# Pixel8x4U.net
KiCad netlist of a schematic drawn in EAGLE
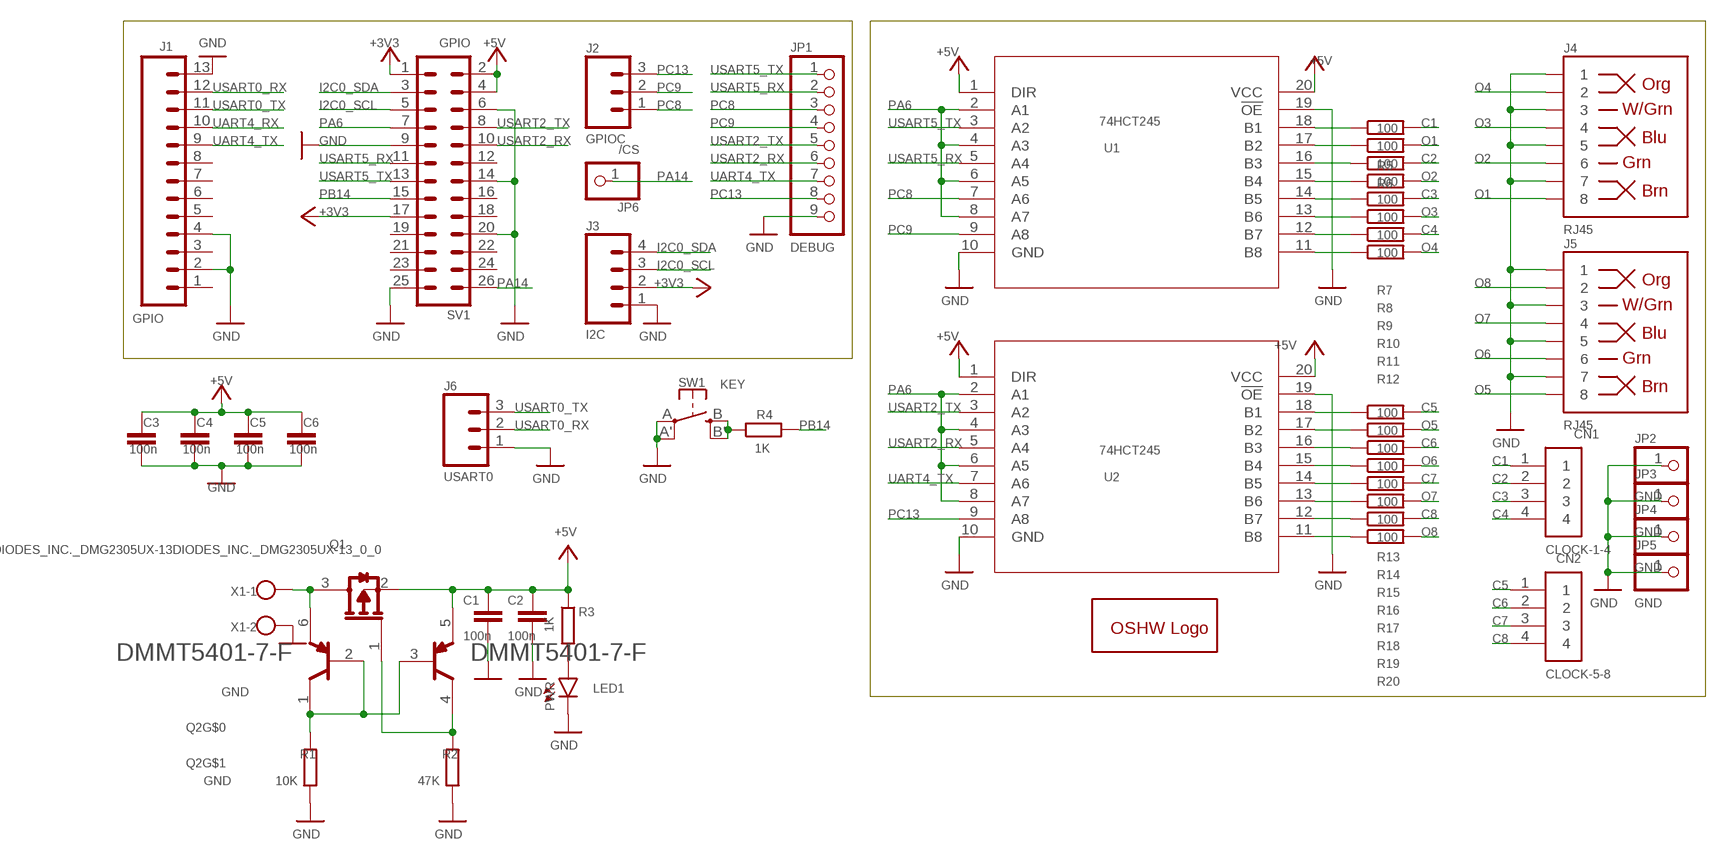
[diagram p0: schematic, sheet 1]

(export (version "E")
  (design (tool "Eeschema 10.0.6"))
  (components
    (comp (ref "C1")
      (value "100n")
      (footprint "eagle-import:C0603")
      (libsource (lib "eagle-import") (part "C-EUC0603"))
    )
    (comp (ref "C2")
      (value "100n")
      (footprint "eagle-import:C0603")
      (libsource (lib "eagle-import") (part "C-EUC0603"))
    )
    (comp (ref "C3")
      (value "100n")
      (footprint "eagle-import:C0603")
      (libsource (lib "eagle-import") (part "C-EUC0603"))
    )
    (comp (ref "C4")
      (value "100n")
      (footprint "eagle-import:C0603")
      (libsource (lib "eagle-import") (part "C-EUC0603"))
    )
    (comp (ref "C5")
      (value "100n")
      (footprint "eagle-import:C0603")
      (libsource (lib "eagle-import") (part "C-EUC0603"))
    )
    (comp (ref "C6")
      (value "100n")
      (footprint "eagle-import:C0603")
      (libsource (lib "eagle-import") (part "C-EUC0603"))
    )
    (comp (ref "CN1")
      (value "CLOCK-1-4")
      (footprint "eagle-import:1X04-CLEANBIG")
      (libsource (lib "eagle-import") (part "1X4-CLEANBIG"))
    )
    (comp (ref "CN2")
      (value "CLOCK-5-8")
      (footprint "eagle-import:1X04-CLEANBIG")
      (libsource (lib "eagle-import") (part "1X4-CLEANBIG"))
    )
    (comp (ref "GOLD_ORB_SM1")
      (value "OSHWLOGOLOGO5MM")
      (footprint "eagle-import:OSHW_5MM")
      (libsource (lib "eagle-import") (part "OSHWLOGOLOGO5MM"))
    )
    (comp (ref "J1")
      (value "GPIO")
      (footprint "eagle-import:1X13")
      (libsource (lib "eagle-import") (part "CONN_13"))
    )
    (comp (ref "J2")
      (value "GPIOC")
      (footprint "eagle-import:1X03")
      (libsource (lib "eagle-import") (part "CONN_03"))
    )
    (comp (ref "J3")
      (value "I2C")
      (footprint "eagle-import:1X04")
      (libsource (lib "eagle-import") (part "CONN_04"))
    )
    (comp (ref "J4")
      (value "RJ45")
      (footprint "eagle-import:RJ45-8")
      (libsource (lib "eagle-import") (part "RJ45-8"))
    )
    (comp (ref "J5")
      (value "RJ45")
      (footprint "eagle-import:RJ45-8")
      (libsource (lib "eagle-import") (part "RJ45-8"))
    )
    (comp (ref "J6")
      (value "USART0")
      (footprint "eagle-import:1X03")
      (libsource (lib "eagle-import") (part "CONN_03"))
    )
    (comp (ref "JP1")
      (value "DEBUG")
      (footprint "eagle-import:1X09")
      (libsource (lib "eagle-import") (part "PINHD-1X9"))
    )
    (comp (ref "JP2")
      (value "GND")
      (footprint "eagle-import:1X01-CLEANBIG")
      (libsource (lib "eagle-import") (part "PINHD-1X1CB"))
    )
    (comp (ref "JP3")
      (value "GND")
      (footprint "eagle-import:1X01-CLEANBIG")
      (libsource (lib "eagle-import") (part "PINHD-1X1CB"))
    )
    (comp (ref "JP4")
      (value "GND")
      (footprint "eagle-import:1X01-CLEANBIG")
      (libsource (lib "eagle-import") (part "PINHD-1X1CB"))
    )
    (comp (ref "JP5")
      (value "GND")
      (footprint "eagle-import:1X01-CLEANBIG")
      (libsource (lib "eagle-import") (part "PINHD-1X1CB"))
    )
    (comp (ref "JP6")
      (value "/CS")
      (footprint "eagle-import:1X01-CLEANBIG")
      (libsource (lib "eagle-import") (part "PINHD-1X1CB"))
    )
    (comp (ref "LED1")
      (value "PWR")
      (footprint "eagle-import:CHIP-LED0603")
      (libsource (lib "eagle-import") (part "LEDCHIP-LED0603"))
    )
    (comp (ref "Q1")
      (value "DIODES_INC._DMG2305UX-13DIODES_INC._DMG2305UX-13_0_0")
      (footprint "eagle-import:DIODES_INC._DMG2305UX-13_0")
      (fields
        (field (name "DIGIKEY_PART_NUMBER") "DMG2305UX-13DICT-ND")
        (field (name "MF") "Diodes Inc.")
        (field (name "MOUSER_PART_NUMBER") "621-DMG2305UX-13")
      )
      (libsource (lib "eagle-import") (part "DIODES_INC._DMG2305UX-13DIODES_INC._DMG2305UX-13_0_0"))
    )
    (comp (ref "Q2")
      (value "DMMT5401-7-F_0_0")
      (footprint "eagle-import:DIODES_DMMT5401-7-F_0")
      (fields
        (field (name "DIGIKEY_PART_NUMBER") "DMMT5401-FDICT-ND")
        (field (name "MF") "Diodes")
        (field (name "MOUSER_PART_NUMBER") "621-DMMT5401-7-F")
      )
      (libsource (lib "eagle-import") (part "DIODES_DMMT5401-7-FDIODES_DMMT5401-7-F_0_0"))
    )
    (comp (ref "R1")
      (value "10K")
      (footprint "eagle-import:R0402")
      (libsource (lib "eagle-import") (part "R-EU_R0402"))
    )
    (comp (ref "R2")
      (value "47K")
      (footprint "eagle-import:R0402")
      (libsource (lib "eagle-import") (part "R-EU_R0402"))
    )
    (comp (ref "R3")
      (value "1K")
      (footprint "eagle-import:R0402")
      (libsource (lib "eagle-import") (part "resistor_348_R-EU_R0402"))
    )
    (comp (ref "R4")
      (value "1K")
      (footprint "eagle-import:R0402")
      (libsource (lib "eagle-import") (part "resistor_348_R-EU_R0402"))
    )
    (comp (ref "R5")
      (value "100")
      (footprint "eagle-import:R0402")
      (libsource (lib "eagle-import") (part "R-EU_R0402"))
    )
    (comp (ref "R6")
      (value "100")
      (footprint "eagle-import:R0402")
      (libsource (lib "eagle-import") (part "R-EU_R0402"))
    )
    (comp (ref "R7")
      (value "100")
      (footprint "eagle-import:R0402")
      (libsource (lib "eagle-import") (part "R-EU_R0402"))
    )
    (comp (ref "R8")
      (value "100")
      (footprint "eagle-import:R0402")
      (libsource (lib "eagle-import") (part "R-EU_R0402"))
    )
    (comp (ref "R9")
      (value "100")
      (footprint "eagle-import:R0402")
      (libsource (lib "eagle-import") (part "R-EU_R0402"))
    )
    (comp (ref "R10")
      (value "100")
      (footprint "eagle-import:R0402")
      (libsource (lib "eagle-import") (part "R-EU_R0402"))
    )
    (comp (ref "R11")
      (value "100")
      (footprint "eagle-import:R0402")
      (libsource (lib "eagle-import") (part "R-EU_R0402"))
    )
    (comp (ref "R12")
      (value "100")
      (footprint "eagle-import:R0402")
      (libsource (lib "eagle-import") (part "R-EU_R0402"))
    )
    (comp (ref "R13")
      (value "100")
      (footprint "eagle-import:R0402")
      (libsource (lib "eagle-import") (part "R-EU_R0402"))
    )
    (comp (ref "R14")
      (value "100")
      (footprint "eagle-import:R0402")
      (libsource (lib "eagle-import") (part "R-EU_R0402"))
    )
    (comp (ref "R15")
      (value "100")
      (footprint "eagle-import:R0402")
      (libsource (lib "eagle-import") (part "R-EU_R0402"))
    )
    (comp (ref "R16")
      (value "100")
      (footprint "eagle-import:R0402")
      (libsource (lib "eagle-import") (part "R-EU_R0402"))
    )
    (comp (ref "R17")
      (value "100")
      (footprint "eagle-import:R0402")
      (libsource (lib "eagle-import") (part "R-EU_R0402"))
    )
    (comp (ref "R18")
      (value "100")
      (footprint "eagle-import:R0402")
      (libsource (lib "eagle-import") (part "R-EU_R0402"))
    )
    (comp (ref "R19")
      (value "100")
      (footprint "eagle-import:R0402")
      (libsource (lib "eagle-import") (part "R-EU_R0402"))
    )
    (comp (ref "R20")
      (value "100")
      (footprint "eagle-import:R0402")
      (libsource (lib "eagle-import") (part "R-EU_R0402"))
    )
    (comp (ref "SV1")
      (value "GPIO")
      (footprint "eagle-import:MA13-2")
      (libsource (lib "eagle-import") (part "MA13-2"))
    )
    (comp (ref "SW1")
      (value "KEY")
      (footprint "eagle-import:EVQ-Q2")
      (libsource (lib "eagle-import") (part "SPST_TACT-EVQQ2"))
    )
    (comp (ref "U1")
      (value "74HCT245")
      (footprint "eagle-import:PW20")
      (fields
        (field (name "GENERIC_PART_NUMBER") "SN74HCT245")
        (field (name "MANUFACTURER") "Texas Instruments")
        (field (name "MANUFACTURER_PART_NUMBER") "SN74HCT245PWR")
      )
      (libsource (lib "eagle-import") (part "SN74HCT245PWR"))
    )
    (comp (ref "U2")
      (value "74HCT245")
      (footprint "eagle-import:PW20")
      (fields
        (field (name "GENERIC_PART_NUMBER") "SN74HCT245")
        (field (name "MANUFACTURER") "Texas Instruments")
        (field (name "MANUFACTURER_PART_NUMBER") "SN74HCT245PWR")
      )
      (libsource (lib "eagle-import") (part "SN74HCT245PWR"))
    )
    (comp (ref "X1")
      (value "W237-102")
      (footprint "eagle-import:W237-102")
      (fields (field (name "MPN") "237-102"))
      (libsource (lib "eagle-import") (part "W237-102"))
    )
  )
  (nets
    (net (code "1") (name "+3V3") (class "Default")
      (node (ref "J3") (pin "2") (pinfunction "2_2") (pintype "passive"))
      (node (ref "SV1") (pin "1") (pinfunction "1_1") (pintype "passive"))
      (node (ref "SV1") (pin "17") (pinfunction "17_17") (pintype "passive"))
    )
    (net (code "2") (name "+5V") (class "Default")
      (node (ref "C1") (pin "1") (pinfunction "1_1") (pintype "passive"))
      (node (ref "C2") (pin "1") (pinfunction "1_1") (pintype "passive"))
      (node (ref "C3") (pin "1") (pinfunction "1_1") (pintype "passive"))
      (node (ref "C4") (pin "1") (pinfunction "1_1") (pintype "passive"))
      (node (ref "C5") (pin "1") (pinfunction "1_1") (pintype "passive"))
      (node (ref "C6") (pin "1") (pinfunction "1_1") (pintype "passive"))
      (node (ref "Q1") (pin "2") (pinfunction "S_2") (pintype "passive"))
      (node (ref "Q2") (pin "5") (pinfunction "E2_5") (pintype "passive"))
      (node (ref "R3") (pin "1") (pinfunction "1_1") (pintype "passive"))
      (node (ref "SV1") (pin "2") (pinfunction "2_2") (pintype "passive"))
      (node (ref "SV1") (pin "4") (pinfunction "4_4") (pintype "passive"))
      (node (ref "U1") (pin "1") (pinfunction "DIR_1") (pintype "input"))
      (node (ref "U1") (pin "20") (pinfunction "VCC_20") (pintype "power_in"))
      (node (ref "U2") (pin "1") (pinfunction "DIR_1") (pintype "input"))
      (node (ref "U2") (pin "20") (pinfunction "VCC_20") (pintype "power_in"))
    )
    (net (code "3") (name "/C1") (class "Default")
      (node (ref "CN1") (pin "1") (pinfunction "1_1") (pintype "bidirectional"))
      (node (ref "R5") (pin "2") (pinfunction "2_2") (pintype "passive"))
    )
    (net (code "4") (name "/C2") (class "Default")
      (node (ref "CN1") (pin "2") (pinfunction "2_2") (pintype "bidirectional"))
      (node (ref "R7") (pin "2") (pinfunction "2_2") (pintype "passive"))
    )
    (net (code "5") (name "/C3") (class "Default")
      (node (ref "CN1") (pin "3") (pinfunction "3_3") (pintype "bidirectional"))
      (node (ref "R9") (pin "2") (pinfunction "2_2") (pintype "passive"))
    )
    (net (code "6") (name "/C4") (class "Default")
      (node (ref "CN1") (pin "4") (pinfunction "4_4") (pintype "bidirectional"))
      (node (ref "R11") (pin "2") (pinfunction "2_2") (pintype "passive"))
    )
    (net (code "7") (name "/C5") (class "Default")
      (node (ref "CN2") (pin "1") (pinfunction "1_1") (pintype "bidirectional"))
      (node (ref "R13") (pin "2") (pinfunction "2_2") (pintype "passive"))
    )
    (net (code "8") (name "/C6") (class "Default")
      (node (ref "CN2") (pin "2") (pinfunction "2_2") (pintype "bidirectional"))
      (node (ref "R15") (pin "2") (pinfunction "2_2") (pintype "passive"))
    )
    (net (code "9") (name "/C7") (class "Default")
      (node (ref "CN2") (pin "3") (pinfunction "3_3") (pintype "bidirectional"))
      (node (ref "R17") (pin "2") (pinfunction "2_2") (pintype "passive"))
    )
    (net (code "10") (name "/C8") (class "Default")
      (node (ref "CN2") (pin "4") (pinfunction "4_4") (pintype "bidirectional"))
      (node (ref "R19") (pin "2") (pinfunction "2_2") (pintype "passive"))
    )
    (net (code "11") (name "/I2C0_SCL") (class "Default")
      (node (ref "J3") (pin "3") (pinfunction "3_3") (pintype "passive"))
      (node (ref "SV1") (pin "5") (pinfunction "5_5") (pintype "passive"))
    )
    (net (code "12") (name "/I2C0_SDA") (class "Default")
      (node (ref "J3") (pin "4") (pinfunction "4_4") (pintype "passive"))
      (node (ref "SV1") (pin "3") (pinfunction "3_3") (pintype "passive"))
    )
    (net (code "13") (name "/O1") (class "Default")
      (node (ref "J4") (pin "8") (pinfunction "8_8") (pintype "bidirectional"))
      (node (ref "R6") (pin "2") (pinfunction "2_2") (pintype "passive"))
    )
    (net (code "14") (name "/O2") (class "Default")
      (node (ref "J4") (pin "6") (pinfunction "6_6") (pintype "bidirectional"))
      (node (ref "R8") (pin "2") (pinfunction "2_2") (pintype "passive"))
    )
    (net (code "15") (name "/O3") (class "Default")
      (node (ref "J4") (pin "4") (pinfunction "4_4") (pintype "bidirectional"))
      (node (ref "R10") (pin "2") (pinfunction "2_2") (pintype "passive"))
    )
    (net (code "16") (name "/O4") (class "Default")
      (node (ref "J4") (pin "2") (pinfunction "2_2") (pintype "bidirectional"))
      (node (ref "R12") (pin "2") (pinfunction "2_2") (pintype "passive"))
    )
    (net (code "17") (name "/O5") (class "Default")
      (node (ref "J5") (pin "8") (pinfunction "8_8") (pintype "bidirectional"))
      (node (ref "R14") (pin "2") (pinfunction "2_2") (pintype "passive"))
    )
    (net (code "18") (name "/O6") (class "Default")
      (node (ref "J5") (pin "6") (pinfunction "6_6") (pintype "bidirectional"))
      (node (ref "R16") (pin "2") (pinfunction "2_2") (pintype "passive"))
    )
    (net (code "19") (name "/O7") (class "Default")
      (node (ref "J5") (pin "4") (pinfunction "4_4") (pintype "bidirectional"))
      (node (ref "R18") (pin "2") (pinfunction "2_2") (pintype "passive"))
    )
    (net (code "20") (name "/O8") (class "Default")
      (node (ref "J5") (pin "2") (pinfunction "2_2") (pintype "bidirectional"))
      (node (ref "R20") (pin "2") (pinfunction "2_2") (pintype "passive"))
    )
    (net (code "21") (name "/PA6") (class "Default")
      (node (ref "SV1") (pin "7") (pinfunction "7_7") (pintype "passive"))
      (node (ref "U1") (pin "2") (pinfunction "A1_2") (pintype "bidirectional"))
      (node (ref "U1") (pin "4") (pinfunction "A3_4") (pintype "bidirectional"))
      (node (ref "U1") (pin "6") (pinfunction "A5_6") (pintype "bidirectional"))
      (node (ref "U1") (pin "8") (pinfunction "A7_8") (pintype "bidirectional"))
      (node (ref "U2") (pin "2") (pinfunction "A1_2") (pintype "bidirectional"))
      (node (ref "U2") (pin "4") (pinfunction "A3_4") (pintype "bidirectional"))
      (node (ref "U2") (pin "6") (pinfunction "A5_6") (pintype "bidirectional"))
      (node (ref "U2") (pin "8") (pinfunction "A7_8") (pintype "bidirectional"))
    )
    (net (code "22") (name "/PA14") (class "Default")
      (node (ref "JP6") (pin "1") (pinfunction "1_1") (pintype "passive"))
      (node (ref "SV1") (pin "26") (pinfunction "26_26") (pintype "passive"))
    )
    (net (code "23") (name "/PB14") (class "Default")
      (node (ref "R4") (pin "2") (pinfunction "2_2") (pintype "passive"))
      (node (ref "SV1") (pin "15") (pinfunction "15_15") (pintype "passive"))
    )
    (net (code "24") (name "/PC8") (class "Default")
      (node (ref "J2") (pin "1") (pinfunction "1_1") (pintype "passive"))
      (node (ref "JP1") (pin "3") (pinfunction "3_3") (pintype "passive"))
      (node (ref "U1") (pin "7") (pinfunction "A6_7") (pintype "bidirectional"))
    )
    (net (code "25") (name "/PC9") (class "Default")
      (node (ref "J2") (pin "2") (pinfunction "2_2") (pintype "passive"))
      (node (ref "JP1") (pin "4") (pinfunction "4_4") (pintype "passive"))
      (node (ref "U1") (pin "9") (pinfunction "A8_9") (pintype "bidirectional"))
    )
    (net (code "26") (name "/PC13") (class "Default")
      (node (ref "J2") (pin "3") (pinfunction "3_3") (pintype "passive"))
      (node (ref "JP1") (pin "8") (pinfunction "8_8") (pintype "passive"))
      (node (ref "U2") (pin "9") (pinfunction "A8_9") (pintype "bidirectional"))
    )
    (net (code "27") (name "/UART4_RX") (class "Default")
      (node (ref "J1") (pin "10") (pinfunction "10_10") (pintype "passive"))
    )
    (net (code "28") (name "/UART4_TX") (class "Default")
      (node (ref "J1") (pin "9") (pinfunction "9_9") (pintype "passive"))
      (node (ref "JP1") (pin "7") (pinfunction "7_7") (pintype "passive"))
      (node (ref "U2") (pin "7") (pinfunction "A6_7") (pintype "bidirectional"))
    )
    (net (code "29") (name "/USART0_RX") (class "Default")
      (node (ref "J1") (pin "12") (pinfunction "12_12") (pintype "passive"))
      (node (ref "J6") (pin "2") (pinfunction "2_2") (pintype "passive"))
    )
    (net (code "30") (name "/USART0_TX") (class "Default")
      (node (ref "J1") (pin "11") (pinfunction "11_11") (pintype "passive"))
      (node (ref "J6") (pin "3") (pinfunction "3_3") (pintype "passive"))
    )
    (net (code "31") (name "/USART2_RX") (class "Default")
      (node (ref "JP1") (pin "6") (pinfunction "6_6") (pintype "passive"))
      (node (ref "SV1") (pin "10") (pinfunction "10_10") (pintype "passive"))
      (node (ref "U2") (pin "5") (pinfunction "A4_5") (pintype "bidirectional"))
    )
    (net (code "32") (name "/USART2_TX") (class "Default")
      (node (ref "JP1") (pin "5") (pinfunction "5_5") (pintype "passive"))
      (node (ref "SV1") (pin "8") (pinfunction "8_8") (pintype "passive"))
      (node (ref "U2") (pin "3") (pinfunction "A2_3") (pintype "bidirectional"))
    )
    (net (code "33") (name "/USART5_RX") (class "Default")
      (node (ref "JP1") (pin "2") (pinfunction "2_2") (pintype "passive"))
      (node (ref "SV1") (pin "11") (pinfunction "11_11") (pintype "passive"))
      (node (ref "U1") (pin "5") (pinfunction "A4_5") (pintype "bidirectional"))
    )
    (net (code "34") (name "/USART5_TX") (class "Default")
      (node (ref "JP1") (pin "1") (pinfunction "1_1") (pintype "passive"))
      (node (ref "SV1") (pin "13") (pinfunction "13_13") (pintype "passive"))
      (node (ref "U1") (pin "3") (pinfunction "A2_3") (pintype "bidirectional"))
    )
    (net (code "35") (name "GND") (class "Default")
      (node (ref "C1") (pin "2") (pinfunction "2_2") (pintype "passive"))
      (node (ref "C2") (pin "2") (pinfunction "2_2") (pintype "passive"))
      (node (ref "C3") (pin "2") (pinfunction "2_2") (pintype "passive"))
      (node (ref "C4") (pin "2") (pinfunction "2_2") (pintype "passive"))
      (node (ref "C5") (pin "2") (pinfunction "2_2") (pintype "passive"))
      (node (ref "C6") (pin "2") (pinfunction "2_2") (pintype "passive"))
      (node (ref "J1") (pin "13") (pinfunction "13_13") (pintype "passive"))
      (node (ref "J1") (pin "2") (pinfunction "2_2") (pintype "passive"))
      (node (ref "J1") (pin "4") (pinfunction "4_4") (pintype "passive"))
      (node (ref "J3") (pin "1") (pinfunction "1_1") (pintype "passive"))
      (node (ref "J4") (pin "1") (pinfunction "1_1") (pintype "bidirectional"))
      (node (ref "J4") (pin "3") (pinfunction "3_3") (pintype "bidirectional"))
      (node (ref "J4") (pin "5") (pinfunction "5_5") (pintype "bidirectional"))
      (node (ref "J4") (pin "7") (pinfunction "7_7") (pintype "bidirectional"))
      (node (ref "J5") (pin "1") (pinfunction "1_1") (pintype "bidirectional"))
      (node (ref "J5") (pin "3") (pinfunction "3_3") (pintype "bidirectional"))
      (node (ref "J5") (pin "5") (pinfunction "5_5") (pintype "bidirectional"))
      (node (ref "J5") (pin "7") (pinfunction "7_7") (pintype "bidirectional"))
      (node (ref "J6") (pin "1") (pinfunction "1_1") (pintype "passive"))
      (node (ref "JP1") (pin "9") (pinfunction "9_9") (pintype "passive"))
      (node (ref "JP2") (pin "1") (pinfunction "1_1") (pintype "passive"))
      (node (ref "JP3") (pin "1") (pinfunction "1_1") (pintype "passive"))
      (node (ref "JP4") (pin "1") (pinfunction "1_1") (pintype "passive"))
      (node (ref "JP5") (pin "1") (pinfunction "1_1") (pintype "passive"))
      (node (ref "LED1") (pin "C") (pinfunction "C_C") (pintype "passive"))
      (node (ref "R1") (pin "1") (pinfunction "1_1") (pintype "passive"))
      (node (ref "R2") (pin "1") (pinfunction "1_1") (pintype "passive"))
      (node (ref "SV1") (pin "14") (pinfunction "14_14") (pintype "passive"))
      (node (ref "SV1") (pin "20") (pinfunction "20_20") (pintype "passive"))
      (node (ref "SV1") (pin "25") (pinfunction "25_25") (pintype "passive"))
      (node (ref "SV1") (pin "6") (pinfunction "6_6") (pintype "passive"))
      (node (ref "SV1") (pin "9") (pinfunction "9_9") (pintype "passive"))
      (node (ref "SW1") (pin "A") (pinfunction "P_A") (pintype "passive"))
      (node (ref "SW1") (pin "A'") (pinfunction "P1_A'") (pintype "passive"))
      (node (ref "U1") (pin "10") (pinfunction "GND_10") (pintype "power_in"))
      (node (ref "U1") (pin "19") (pinfunction "~{OE}_19") (pintype "input"))
      (node (ref "U2") (pin "10") (pinfunction "GND_10") (pintype "power_in"))
      (node (ref "U2") (pin "19") (pinfunction "~{OE}_19") (pintype "input"))
      (node (ref "X1") (pin "2") (pinfunction "KL_2") (pintype "passive"))
    )
    (net (code "36") (name "Net-(LED1-PadA)") (class "Default")
      (node (ref "LED1") (pin "A") (pinfunction "A_A") (pintype "passive"))
      (node (ref "R3") (pin "2") (pinfunction "2_2") (pintype "passive"))
    )
    (net (code "37") (name "Net-(Q1-D)") (class "Default")
      (node (ref "Q1") (pin "3") (pinfunction "D_3") (pintype "passive"))
      (node (ref "Q2") (pin "6") (pinfunction "E1_6") (pintype "passive"))
      (node (ref "X1") (pin "1") (pinfunction "KL_1") (pintype "passive"))
    )
    (net (code "38") (name "Net-(Q1-G)") (class "Default")
      (node (ref "Q1") (pin "1") (pinfunction "G_1") (pintype "passive"))
      (node (ref "Q2") (pin "4") (pinfunction "C2_4") (pintype "passive"))
      (node (ref "R2") (pin "2") (pinfunction "2_2") (pintype "passive"))
    )
    (net (code "39") (name "Net-(Q2A-B1)") (class "Default")
      (node (ref "Q2") (pin "1") (pinfunction "C1_1") (pintype "passive"))
      (node (ref "Q2") (pin "2") (pinfunction "B1_2") (pintype "passive"))
      (node (ref "Q2") (pin "3") (pinfunction "B2_3") (pintype "passive"))
      (node (ref "R1") (pin "2") (pinfunction "2_2") (pintype "passive"))
    )
    (net (code "40") (name "Net-(SW1-S)") (class "Default")
      (node (ref "R4") (pin "1") (pinfunction "1_1") (pintype "passive"))
      (node (ref "SW1") (pin "B") (pinfunction "S_B") (pintype "passive"))
      (node (ref "SW1") (pin "B'") (pinfunction "S1_B'") (pintype "passive"))
    )
    (net (code "41") (name "Net-(U1-B1)") (class "Default")
      (node (ref "R5") (pin "1") (pinfunction "1_1") (pintype "passive"))
      (node (ref "U1") (pin "18") (pinfunction "B1_18") (pintype "bidirectional"))
    )
    (net (code "42") (name "Net-(U1-B2)") (class "Default")
      (node (ref "R6") (pin "1") (pinfunction "1_1") (pintype "passive"))
      (node (ref "U1") (pin "17") (pinfunction "B2_17") (pintype "bidirectional"))
    )
    (net (code "43") (name "Net-(U1-B3)") (class "Default")
      (node (ref "R7") (pin "1") (pinfunction "1_1") (pintype "passive"))
      (node (ref "U1") (pin "16") (pinfunction "B3_16") (pintype "bidirectional"))
    )
    (net (code "44") (name "Net-(U1-B4)") (class "Default")
      (node (ref "R8") (pin "1") (pinfunction "1_1") (pintype "passive"))
      (node (ref "U1") (pin "15") (pinfunction "B4_15") (pintype "bidirectional"))
    )
    (net (code "45") (name "Net-(U1-B5)") (class "Default")
      (node (ref "R9") (pin "1") (pinfunction "1_1") (pintype "passive"))
      (node (ref "U1") (pin "14") (pinfunction "B5_14") (pintype "bidirectional"))
    )
    (net (code "46") (name "Net-(U1-B6)") (class "Default")
      (node (ref "R10") (pin "1") (pinfunction "1_1") (pintype "passive"))
      (node (ref "U1") (pin "13") (pinfunction "B6_13") (pintype "bidirectional"))
    )
    (net (code "47") (name "Net-(U1-B7)") (class "Default")
      (node (ref "R11") (pin "1") (pinfunction "1_1") (pintype "passive"))
      (node (ref "U1") (pin "12") (pinfunction "B7_12") (pintype "bidirectional"))
    )
    (net (code "48") (name "Net-(U1-B8)") (class "Default")
      (node (ref "R12") (pin "1") (pinfunction "1_1") (pintype "passive"))
      (node (ref "U1") (pin "11") (pinfunction "B8_11") (pintype "bidirectional"))
    )
    (net (code "49") (name "Net-(U2-B1)") (class "Default")
      (node (ref "R13") (pin "1") (pinfunction "1_1") (pintype "passive"))
      (node (ref "U2") (pin "18") (pinfunction "B1_18") (pintype "bidirectional"))
    )
    (net (code "50") (name "Net-(U2-B2)") (class "Default")
      (node (ref "R14") (pin "1") (pinfunction "1_1") (pintype "passive"))
      (node (ref "U2") (pin "17") (pinfunction "B2_17") (pintype "bidirectional"))
    )
    (net (code "51") (name "Net-(U2-B3)") (class "Default")
      (node (ref "R15") (pin "1") (pinfunction "1_1") (pintype "passive"))
      (node (ref "U2") (pin "16") (pinfunction "B3_16") (pintype "bidirectional"))
    )
    (net (code "52") (name "Net-(U2-B4)") (class "Default")
      (node (ref "R16") (pin "1") (pinfunction "1_1") (pintype "passive"))
      (node (ref "U2") (pin "15") (pinfunction "B4_15") (pintype "bidirectional"))
    )
    (net (code "53") (name "Net-(U2-B5)") (class "Default")
      (node (ref "R17") (pin "1") (pinfunction "1_1") (pintype "passive"))
      (node (ref "U2") (pin "14") (pinfunction "B5_14") (pintype "bidirectional"))
    )
    (net (code "54") (name "Net-(U2-B6)") (class "Default")
      (node (ref "R18") (pin "1") (pinfunction "1_1") (pintype "passive"))
      (node (ref "U2") (pin "13") (pinfunction "B6_13") (pintype "bidirectional"))
    )
    (net (code "55") (name "Net-(U2-B7)") (class "Default")
      (node (ref "R19") (pin "1") (pinfunction "1_1") (pintype "passive"))
      (node (ref "U2") (pin "12") (pinfunction "B7_12") (pintype "bidirectional"))
    )
    (net (code "56") (name "Net-(U2-B8)") (class "Default")
      (node (ref "R20") (pin "1") (pinfunction "1_1") (pintype "passive"))
      (node (ref "U2") (pin "11") (pinfunction "B8_11") (pintype "bidirectional"))
    )
    (net (code "57") (name "unconnected-(J1-Pad1)") (class "Default")
      (node (ref "J1") (pin "1") (pinfunction "1_1") (pintype "passive"))
    )
    (net (code "58") (name "unconnected-(J1-Pad3)") (class "Default")
      (node (ref "J1") (pin "3") (pinfunction "3_3") (pintype "passive"))
    )
    (net (code "59") (name "unconnected-(J1-Pad5)") (class "Default")
      (node (ref "J1") (pin "5") (pinfunction "5_5") (pintype "passive"))
    )
    (net (code "60") (name "unconnected-(J1-Pad6)") (class "Default")
      (node (ref "J1") (pin "6") (pinfunction "6_6") (pintype "passive"))
    )
    (net (code "61") (name "unconnected-(J1-Pad7)") (class "Default")
      (node (ref "J1") (pin "7") (pinfunction "7_7") (pintype "passive"))
    )
    (net (code "62") (name "unconnected-(J1-Pad8)") (class "Default")
      (node (ref "J1") (pin "8") (pinfunction "8_8") (pintype "passive"))
    )
    (net (code "63") (name "unconnected-(SV1-Pad12)") (class "Default")
      (node (ref "SV1") (pin "12") (pinfunction "12_12") (pintype "passive"))
    )
    (net (code "64") (name "unconnected-(SV1-Pad16)") (class "Default")
      (node (ref "SV1") (pin "16") (pinfunction "16_16") (pintype "passive"))
    )
    (net (code "65") (name "unconnected-(SV1-Pad18)") (class "Default")
      (node (ref "SV1") (pin "18") (pinfunction "18_18") (pintype "passive"))
    )
    (net (code "66") (name "unconnected-(SV1-Pad19)") (class "Default")
      (node (ref "SV1") (pin "19") (pinfunction "19_19") (pintype "passive"))
    )
    (net (code "67") (name "unconnected-(SV1-Pad21)") (class "Default")
      (node (ref "SV1") (pin "21") (pinfunction "21_21") (pintype "passive"))
    )
    (net (code "68") (name "unconnected-(SV1-Pad22)") (class "Default")
      (node (ref "SV1") (pin "22") (pinfunction "22_22") (pintype "passive"))
    )
    (net (code "69") (name "unconnected-(SV1-Pad23)") (class "Default")
      (node (ref "SV1") (pin "23") (pinfunction "23_23") (pintype "passive"))
    )
    (net (code "70") (name "unconnected-(SV1-Pad24)") (class "Default")
      (node (ref "SV1") (pin "24") (pinfunction "24_24") (pintype "passive"))
    )
  )
)
